# Main.net
KiCad netlist of a schematic drawn in Altium Designer
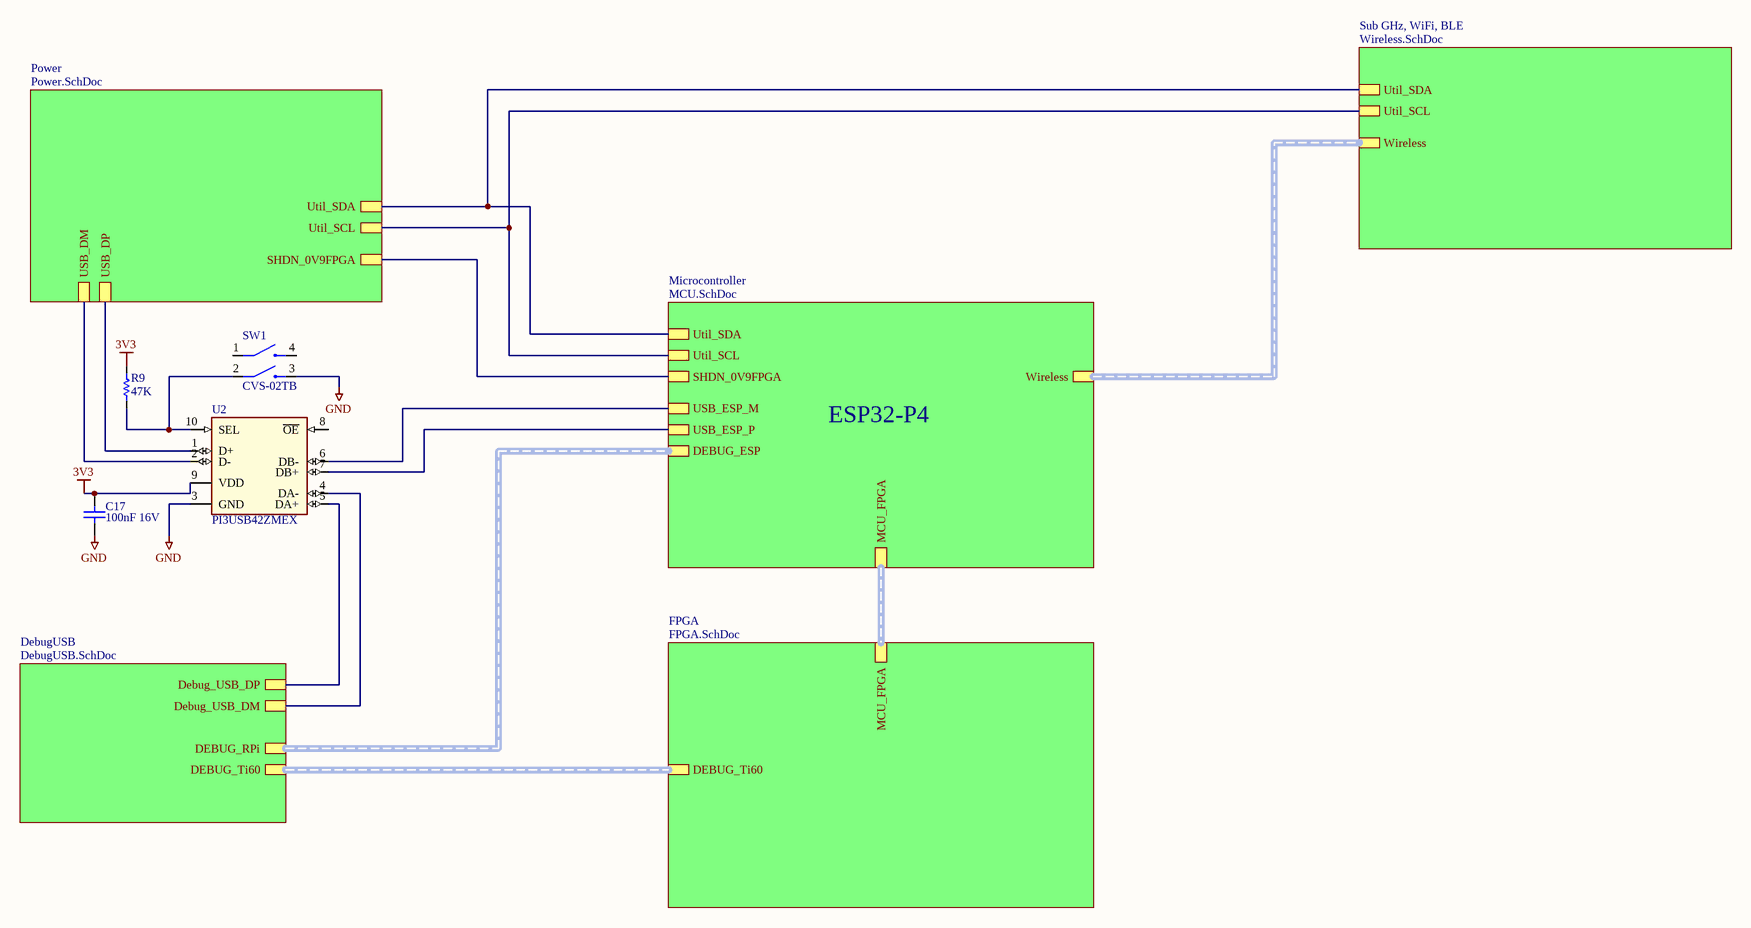
[diagram p0: Main.SchDoc]

(export (version "E")
  (design (tool "Eeschema 10.0.6"))
  (components
    (comp (ref "C17") (value "100nF 16V") (footprint "0402") (libsource (lib "Revolve NTNU") (part "CAP")))
    (comp (ref "R9")
      (value "47K")
      (footprint "0603 Resistor")
      (description "47K, 1%, 1/10W, 0603")
      (libsource (lib "Revolve NTNU") (part "Resistor"))
    )
    (comp (ref "SW1")
      (value "CVS-02TB")
      (footprint "CVS-02TB-Footprint-1")
      (description "SWITCH SLIDE DIP SPST 100MA 6V")
      (libsource (lib "Revolve NTNU") (part "Component_1"))
    )
    (comp (ref "U2")
      (value "PI3USB42ZMEX")
      (footprint "QFN40P140X180X60-10N")
      (description "USB Switch IC 1 Channel 10-UQFN (1.8x1.4)")
      (fields (field (name "MF") "Diodes Inc."))
      (libsource (lib "Handheld") (part "PI3USB42ZMEX"))
    )
  )
  (nets
    (net (code "3") (name "/Debug_USB_DM") (class "Default")
      (node (ref "U2") (pin "4") (pinfunction "DA-_4") (pintype "bidirectional"))
    )
    (net (code "4") (name "/Debug_USB_DP") (class "Default")
      (node (ref "U2") (pin "5") (pinfunction "DA+_5") (pintype "bidirectional"))
    )
    (net (code "7") (name "/USB_DM") (class "Default")
      (node (ref "U2") (pin "2") (pinfunction "D-_2") (pintype "bidirectional"))
    )
    (net (code "8") (name "/USB_DP") (class "Default")
      (node (ref "U2") (pin "1") (pinfunction "D+_1") (pintype "bidirectional"))
    )
    (net (code "9") (name "/USB_ESP_M") (class "Default")
      (node (ref "U2") (pin "6") (pinfunction "DB-_6") (pintype "bidirectional"))
    )
    (net (code "10") (name "/USB_ESP_P") (class "Default")
      (node (ref "U2") (pin "7") (pinfunction "DB+_7") (pintype "bidirectional"))
    )
    (net (code "14") (name "3V3") (class "Default")
      (node (ref "C17") (pin "2") (pinfunction "2_2") (pintype "passive"))
      (node (ref "R9") (pin "1") (pinfunction "1_1") (pintype "passive"))
      (node (ref "U2") (pin "9") (pinfunction "VDD_9") (pintype "power_in"))
    )
    (net (code "15") (name "GND") (class "Default")
      (node (ref "C17") (pin "1") (pinfunction "1_1") (pintype "passive"))
      (node (ref "SW1") (pin "3") (pinfunction "3_3") (pintype "power_in"))
      (node (ref "U2") (pin "3") (pinfunction "GND_3") (pintype "power_in"))
    )
    (net (code "16") (name "Net-(U2-SEL)") (class "Default")
      (node (ref "R9") (pin "2") (pinfunction "2_2") (pintype "passive"))
      (node (ref "SW1") (pin "2") (pinfunction "2_2") (pintype "power_in"))
      (node (ref "U2") (pin "10") (pinfunction "SEL_10") (pintype "input"))
    )
    (net (code "17") (name "unconnected-(SW1-Pad1)") (class "Default")
      (node (ref "SW1") (pin "1") (pinfunction "1_1") (pintype "power_in"))
    )
    (net (code "18") (name "unconnected-(SW1-Pad4)") (class "Default")
      (node (ref "SW1") (pin "4") (pinfunction "4_4") (pintype "power_in"))
    )
    (net (code "19") (name "unconnected-(U2-~{OE}-Pad8)") (class "Default")
      (node (ref "U2") (pin "8") (pinfunction "~{OE}_8") (pintype "input"))
    )
  )
)
